# ESPLEDCTRL.net
KiCad netlist of a schematic drawn in EAGLE
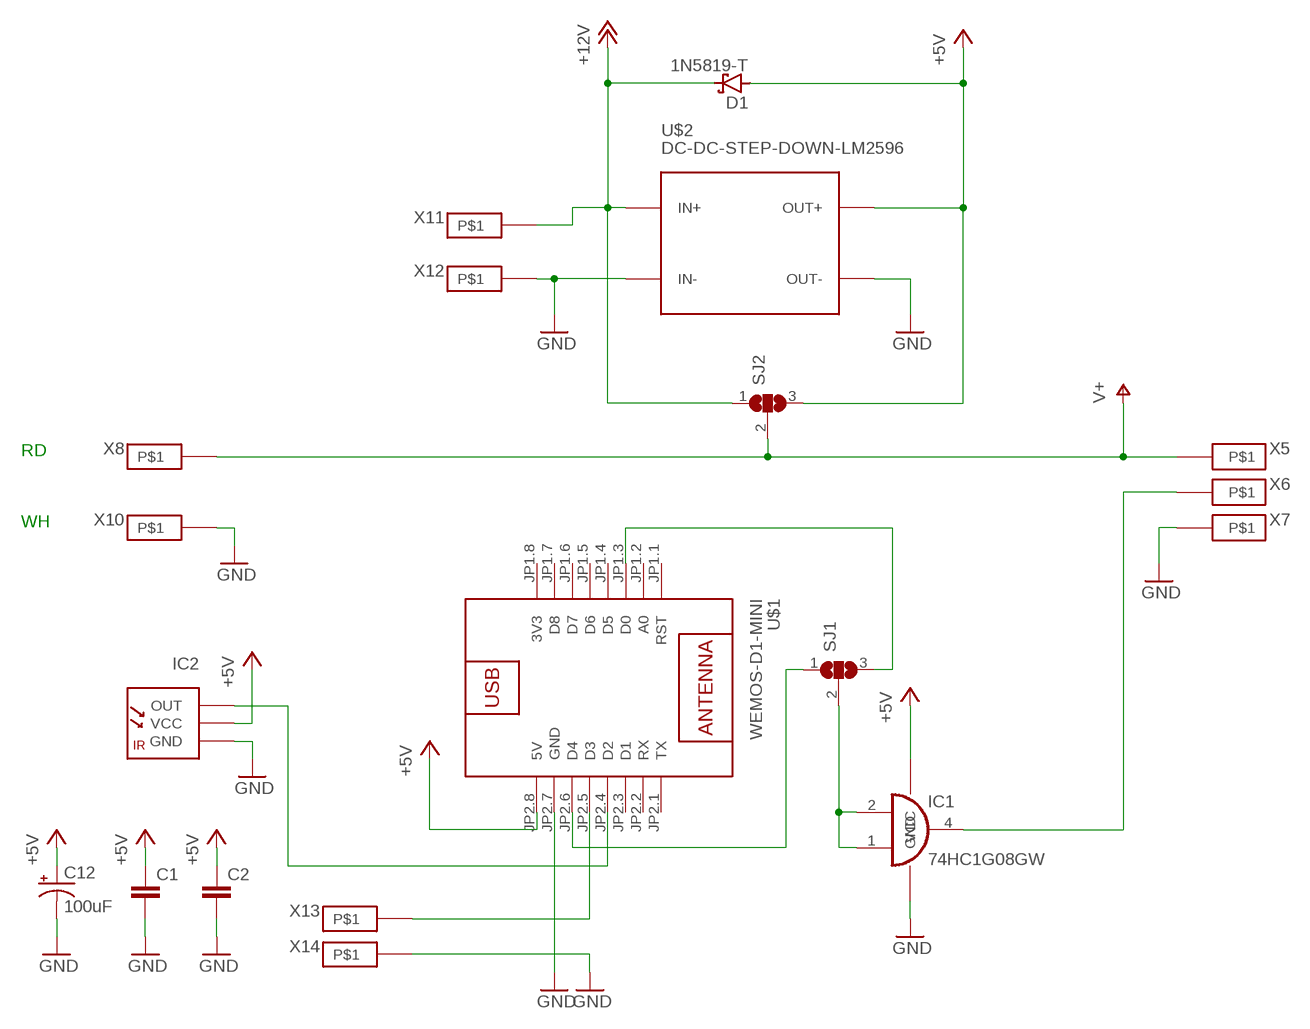
[diagram p0: schematic, sheet 1]

(export (version "E")
  (design (tool "Eeschema 10.0.6"))
  (components
    (comp (ref "C1")
      (value "C-EUC1206")
      (footprint "eagle-import:C1206")
      (libsource (lib "eagle-import") (part "C-EUC1206"))
    )
    (comp (ref "C2")
      (value "C-EUC1206")
      (footprint "eagle-import:C1206")
      (libsource (lib "eagle-import") (part "C-EUC1206"))
    )
    (comp (ref "C12")
      (value "100uF")
      (footprint "eagle-import:PANASONIC_D")
      (libsource (lib "eagle-import") (part "CPOL-USD"))
    )
    (comp (ref "D1")
      (value "1N5819-T")
      (footprint "eagle-import:DO41-7.6")
      (libsource (lib "eagle-import") (part "1N5819-T"))
    )
    (comp (ref "IC1")
      (value "74HC1G08GW")
      (footprint "eagle-import:SOT353")
      (libsource (lib "eagle-import") (part "74HC1G08GW"))
    )
    (comp (ref "IC2")
      (value "TSOP382")
      (footprint "eagle-import:TSOP38")
      (libsource (lib "eagle-import") (part "TSOP382"))
    )
    (comp (ref "SJ1")
      (value "SJ2W")
      (footprint "eagle-import:SJ_2")
      (libsource (lib "eagle-import") (part "SJ2W"))
    )
    (comp (ref "SJ2")
      (value "SJ2W")
      (footprint "eagle-import:SJ_2")
      (libsource (lib "eagle-import") (part "SJ2W"))
    )
    (comp (ref "U$1")
      (value "WEMOS-D1-MINI")
      (footprint "eagle-import:WEMOS-D1-MINI")
      (libsource (lib "eagle-import") (part "WEMOS-D1-MINI"))
    )
    (comp (ref "U$2")
      (value "DC-DC-STEP-DOWN-LM2596")
      (footprint "eagle-import:DC-DC-STEP-DOWN-LM2596")
      (libsource (lib "eagle-import") (part "DC-DC-STEP-DOWN-LM2596"))
    )
    (comp (ref "X5")
      (value "PAD2X4")
      (footprint "eagle-import:PAD2X4")
      (libsource (lib "eagle-import") (part "PAD2X4"))
    )
    (comp (ref "X6")
      (value "PAD2X4")
      (footprint "eagle-import:PAD2X4")
      (libsource (lib "eagle-import") (part "PAD2X4"))
    )
    (comp (ref "X7")
      (value "PAD2X4")
      (footprint "eagle-import:PAD2X4")
      (libsource (lib "eagle-import") (part "PAD2X4"))
    )
    (comp (ref "X8")
      (value "PAD2X4")
      (footprint "eagle-import:PAD2X4")
      (libsource (lib "eagle-import") (part "PAD2X4"))
    )
    (comp (ref "X10")
      (value "PAD2X4")
      (footprint "eagle-import:PAD2X4")
      (libsource (lib "eagle-import") (part "PAD2X4"))
    )
    (comp (ref "X11")
      (value "PAD2X4")
      (footprint "eagle-import:PAD2X4")
      (libsource (lib "eagle-import") (part "PAD2X4"))
    )
    (comp (ref "X12")
      (value "PAD2X4")
      (footprint "eagle-import:PAD2X4")
      (libsource (lib "eagle-import") (part "PAD2X4"))
    )
    (comp (ref "X13")
      (value "PAD2X4")
      (footprint "eagle-import:PAD2X4")
      (libsource (lib "eagle-import") (part "PAD2X4"))
    )
    (comp (ref "X14")
      (value "PAD2X4")
      (footprint "eagle-import:PAD2X4")
      (libsource (lib "eagle-import") (part "PAD2X4"))
    )
  )
  (nets
    (net (code "1") (name "+5V") (class "Default")
      (node (ref "C1") (pin "1") (pinfunction "1_1") (pintype "passive"))
      (node (ref "C12") (pin "+") (pinfunction "+_+") (pintype "passive"))
      (node (ref "C2") (pin "1") (pinfunction "1_1") (pintype "passive"))
      (node (ref "D1") (pin "A") (pinfunction "A_A") (pintype "passive"))
      (node (ref "IC1") (pin "5") (pinfunction "VCC_5") (pintype "power_in"))
      (node (ref "IC2") (pin "3") (pinfunction "VCC_3") (pintype "bidirectional"))
      (node (ref "SJ2") (pin "3") (pinfunction "3_3") (pintype "passive"))
      (node (ref "U$1") (pin "JP2.8") (pinfunction "5V_JP2.8") (pintype "power_in"))
      (node (ref "U$2") (pin "OUT+") (pinfunction "OUT+_OUT+") (pintype "bidirectional"))
    )
    (net (code "2") (name "+12V") (class "Default")
      (node (ref "D1") (pin "C") (pinfunction "C_C") (pintype "passive"))
      (node (ref "SJ2") (pin "1") (pinfunction "1_1") (pintype "passive"))
      (node (ref "U$2") (pin "IN+") (pinfunction "IN+_IN+") (pintype "bidirectional"))
      (node (ref "X11") (pin "P$1") (pinfunction "P$1_P$1") (pintype "bidirectional"))
    )
    (net (code "3") (name "/3V3") (class "Default")
      (node (ref "U$1") (pin "JP1.8") (pinfunction "3V3_JP1.8") (pintype "power_in"))
    )
    (net (code "4") (name "GND") (class "Default")
      (node (ref "C1") (pin "2") (pinfunction "2_2") (pintype "passive"))
      (node (ref "C12") (pin "-") (pinfunction "-_-") (pintype "passive"))
      (node (ref "C2") (pin "2") (pinfunction "2_2") (pintype "passive"))
      (node (ref "IC1") (pin "3") (pinfunction "GND_3") (pintype "power_in"))
      (node (ref "IC2") (pin "2") (pinfunction "GND_2") (pintype "bidirectional"))
      (node (ref "U$1") (pin "JP2.7") (pinfunction "GND_JP2.7") (pintype "power_in"))
      (node (ref "U$2") (pin "IN-") (pinfunction "IN-_IN-") (pintype "bidirectional"))
      (node (ref "U$2") (pin "OUT-") (pinfunction "OUT-_OUT-") (pintype "bidirectional"))
      (node (ref "X10") (pin "P$1") (pinfunction "P$1_P$1") (pintype "bidirectional"))
      (node (ref "X12") (pin "P$1") (pinfunction "P$1_P$1") (pintype "bidirectional"))
      (node (ref "X14") (pin "P$1") (pinfunction "P$1_P$1") (pintype "bidirectional"))
      (node (ref "X7") (pin "P$1") (pinfunction "P$1_P$1") (pintype "bidirectional"))
    )
    (net (code "5") (name "Net-(IC1-I0)") (class "Default")
      (node (ref "IC1") (pin "1") (pinfunction "I1_1") (pintype "input"))
      (node (ref "IC1") (pin "2") (pinfunction "I0_2") (pintype "input"))
      (node (ref "SJ1") (pin "2") (pinfunction "2_2") (pintype "passive"))
    )
    (net (code "6") (name "Net-(IC1-O)") (class "Default")
      (node (ref "IC1") (pin "4") (pinfunction "O_4") (pintype "output"))
      (node (ref "X6") (pin "P$1") (pinfunction "P$1_P$1") (pintype "bidirectional"))
    )
    (net (code "7") (name "Net-(IC2-OUT)") (class "Default")
      (node (ref "IC2") (pin "1") (pinfunction "OUT_1") (pintype "bidirectional"))
      (node (ref "U$1") (pin "JP2.4") (pinfunction "D2_JP2.4") (pintype "bidirectional"))
    )
    (net (code "8") (name "Net-(U$1-D0)") (class "Default")
      (node (ref "SJ1") (pin "3") (pinfunction "3_3") (pintype "passive"))
      (node (ref "U$1") (pin "JP1.3") (pinfunction "D0_JP1.3") (pintype "bidirectional"))
    )
    (net (code "9") (name "Net-(U$1-D3)") (class "Default")
      (node (ref "U$1") (pin "JP2.5") (pinfunction "D3_JP2.5") (pintype "bidirectional"))
      (node (ref "X13") (pin "P$1") (pinfunction "P$1_P$1") (pintype "bidirectional"))
    )
    (net (code "10") (name "Net-(U$1-D4)") (class "Default")
      (node (ref "SJ1") (pin "1") (pinfunction "1_1") (pintype "passive"))
      (node (ref "U$1") (pin "JP2.6") (pinfunction "D4_JP2.6") (pintype "bidirectional"))
    )
    (net (code "11") (name "V+") (class "Default")
      (node (ref "SJ2") (pin "2") (pinfunction "2_2") (pintype "passive"))
      (node (ref "X5") (pin "P$1") (pinfunction "P$1_P$1") (pintype "bidirectional"))
      (node (ref "X8") (pin "P$1") (pinfunction "P$1_P$1") (pintype "bidirectional"))
    )
    (net (code "12") (name "unconnected-(U$1-A0-PadJP1.2)") (class "Default")
      (node (ref "U$1") (pin "JP1.2") (pinfunction "A0_JP1.2") (pintype "bidirectional"))
    )
    (net (code "13") (name "unconnected-(U$1-D1-PadJP2.3)") (class "Default")
      (node (ref "U$1") (pin "JP2.3") (pinfunction "D1_JP2.3") (pintype "bidirectional"))
    )
    (net (code "14") (name "unconnected-(U$1-D5-PadJP1.4)") (class "Default")
      (node (ref "U$1") (pin "JP1.4") (pinfunction "D5_JP1.4") (pintype "bidirectional"))
    )
    (net (code "15") (name "unconnected-(U$1-D6-PadJP1.5)") (class "Default")
      (node (ref "U$1") (pin "JP1.5") (pinfunction "D6_JP1.5") (pintype "bidirectional"))
    )
    (net (code "16") (name "unconnected-(U$1-D7-PadJP1.6)") (class "Default")
      (node (ref "U$1") (pin "JP1.6") (pinfunction "D7_JP1.6") (pintype "bidirectional"))
    )
    (net (code "17") (name "unconnected-(U$1-D8-PadJP1.7)") (class "Default")
      (node (ref "U$1") (pin "JP1.7") (pinfunction "D8_JP1.7") (pintype "bidirectional"))
    )
    (net (code "18") (name "unconnected-(U$1-RST-PadJP1.1)") (class "Default")
      (node (ref "U$1") (pin "JP1.1") (pinfunction "RST_JP1.1") (pintype "bidirectional"))
    )
    (net (code "19") (name "unconnected-(U$1-RX-PadJP2.2)") (class "Default")
      (node (ref "U$1") (pin "JP2.2") (pinfunction "RX_JP2.2") (pintype "bidirectional"))
    )
    (net (code "20") (name "unconnected-(U$1-TX-PadJP2.1)") (class "Default")
      (node (ref "U$1") (pin "JP2.1") (pinfunction "TX_JP2.1") (pintype "bidirectional"))
    )
  )
)
